# Motherboard.net
KiCad netlist of a schematic drawn in Altium Designer
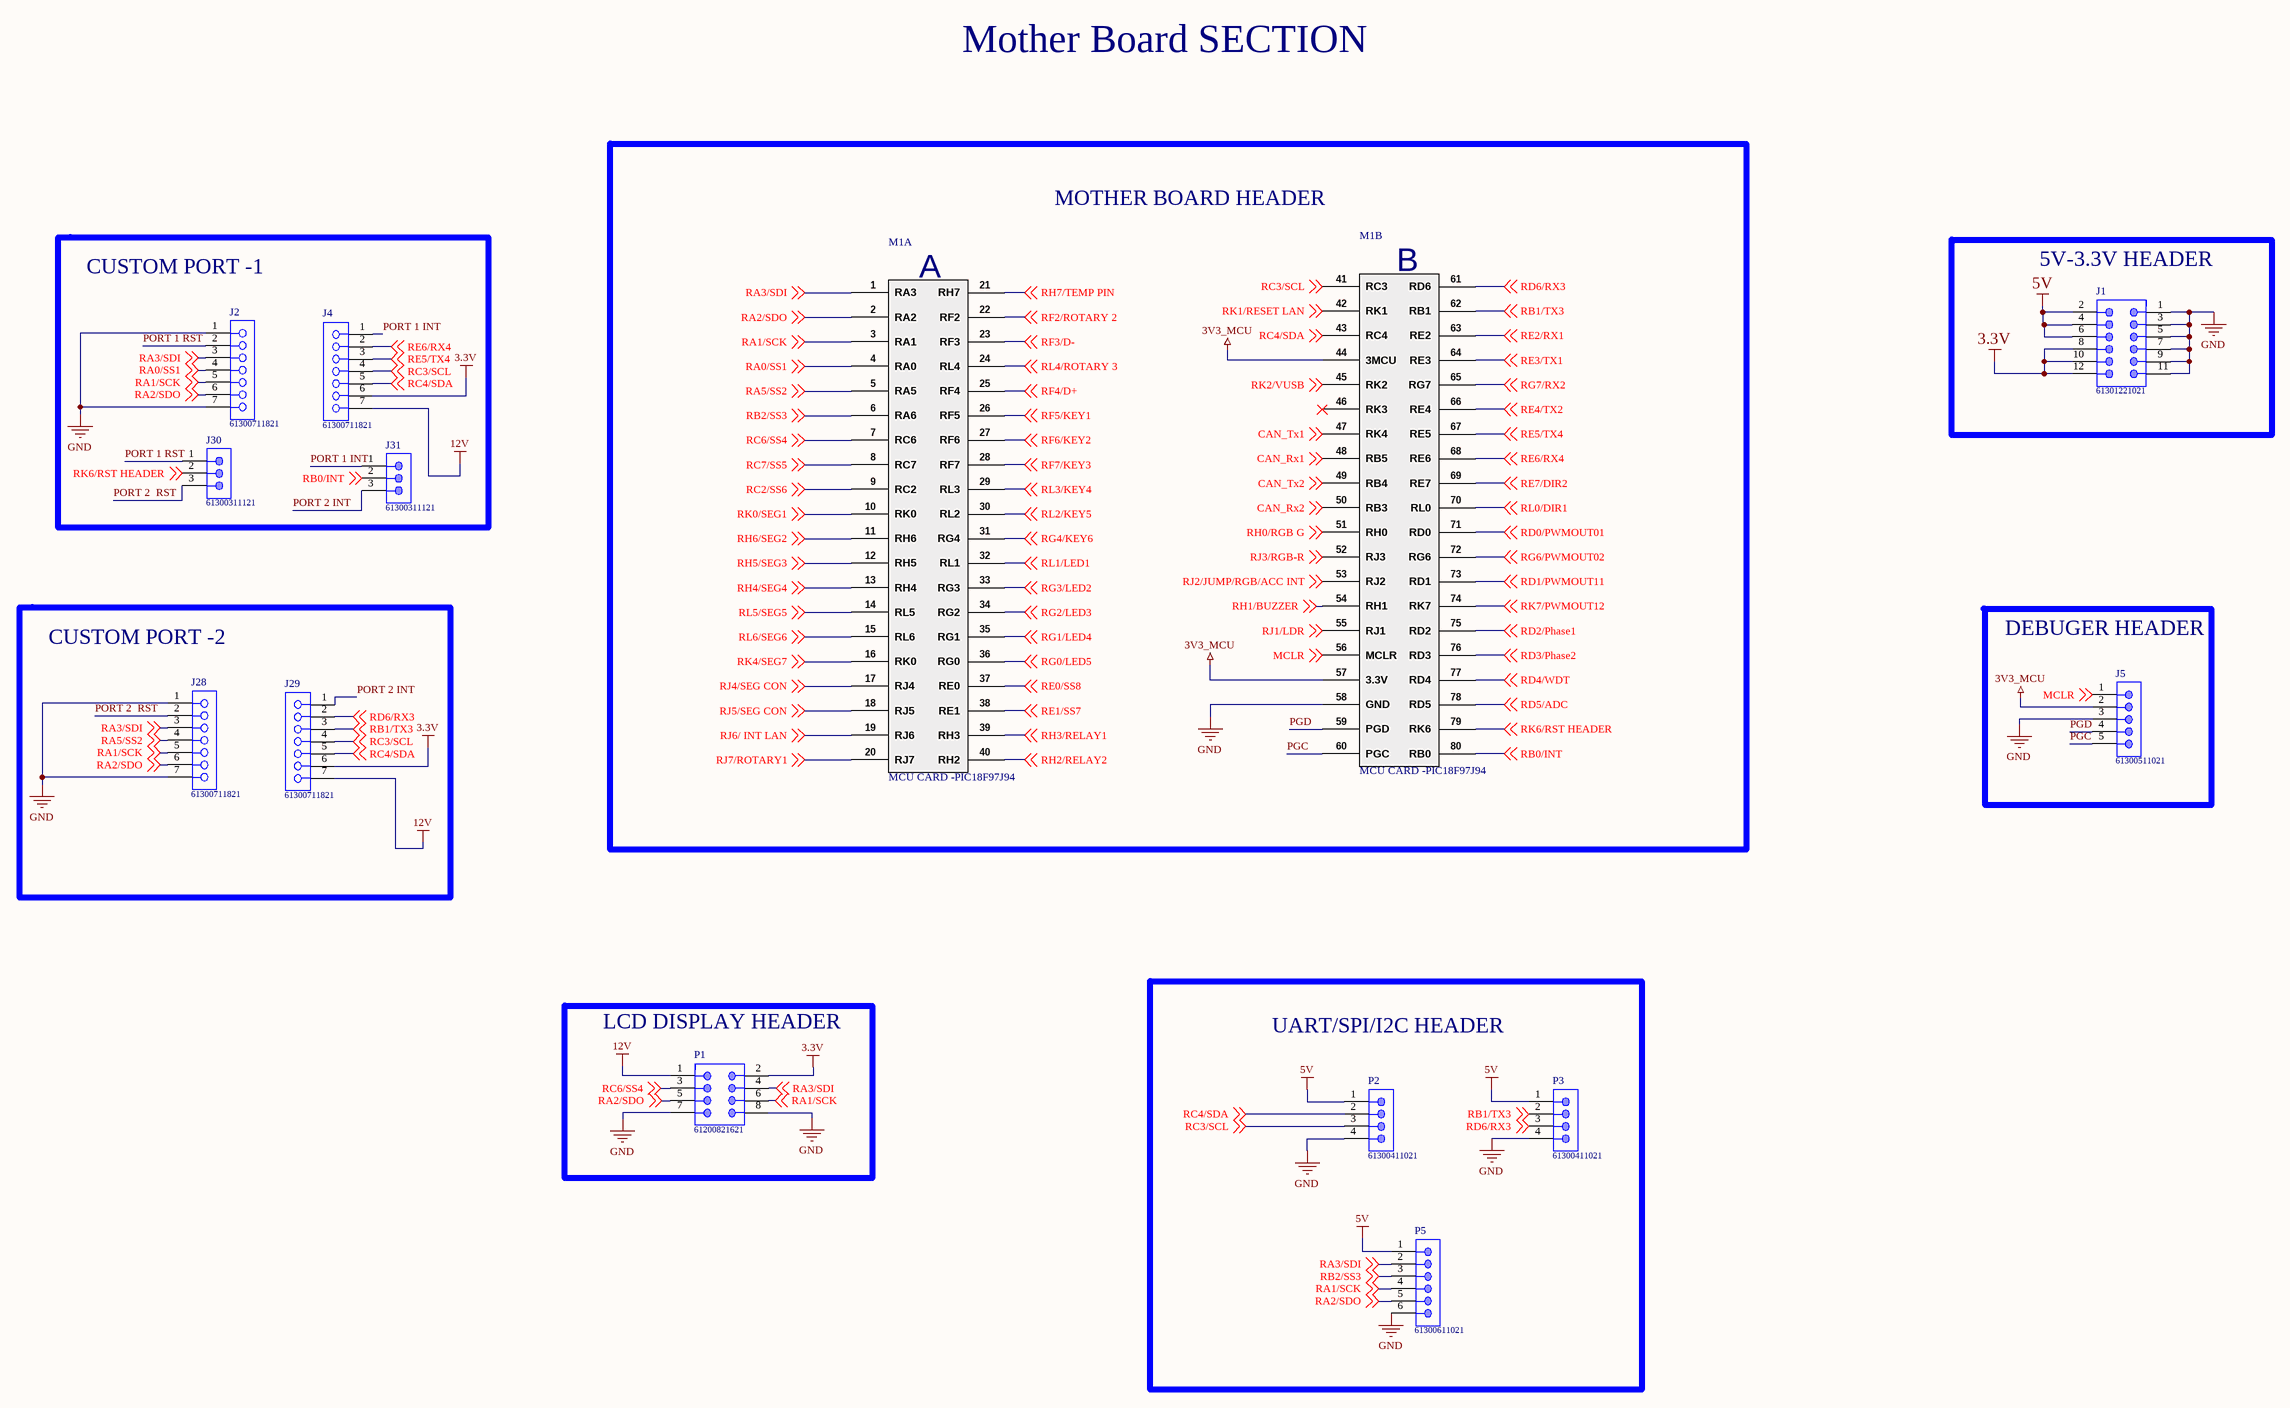
[diagram p0: Motherboard.SchDoc]

(export (version "E")
  (design (tool "Eeschema 10.0.6"))
  (components
    (comp (ref "J1")
      (value "61301221021")
      (footprint "61301221021")
      (description "WR-PHD Pin Header, THT, pitch 2.54mm, Dual Row, Angled, 12pin")
      (fields (field (name "PUBLISHER") "Wurth Elektronik"))
      (libsource (lib "SIL_Connectors WR-PHD_rev19a") (part "61301221021"))
    )
    (comp (ref "J2")
      (value "61300711821")
      (footprint "61300711821")
      (description "WR-PHD Socket Header, THT, pitch 2.54mm, Single Row, Vertical, 7pin")
      (fields (field (name "PUBLISHER") "Wurth Elektronik"))
      (libsource (lib "SIL_Connectors WR-PHD_rev19a") (part "61300711821"))
    )
    (comp (ref "J4")
      (value "61300711821")
      (footprint "61300711821")
      (description "WR-PHD Socket Header, THT, pitch 2.54mm, Single Row, Vertical, 7pin")
      (fields (field (name "PUBLISHER") "Wurth Elektronik"))
      (libsource (lib "SIL_Connectors WR-PHD_rev19a") (part "61300711821"))
    )
    (comp (ref "J5")
      (value "61300511021")
      (footprint "61300511021")
      (description "WR-PHD Pin Header, THT, pitch 2.54mm, Single Row, Angled, 5pin")
      (fields (field (name "PUBLISHER") "Wurth Elektronik"))
      (libsource (lib "SIL_Connectors WR-PHD_rev19a") (part "61300511021"))
    )
    (comp (ref "J28")
      (value "61300711821")
      (footprint "61300711821")
      (description "WR-PHD Socket Header, THT, pitch 2.54mm, Single Row, Vertical, 7pin")
      (fields (field (name "PUBLISHER") "Wurth Elektronik"))
      (libsource (lib "SIL_Connectors WR-PHD_rev19a") (part "61300711821"))
    )
    (comp (ref "J29")
      (value "61300711821")
      (footprint "61300711821")
      (description "WR-PHD Socket Header, THT, pitch 2.54mm, Single Row, Vertical, 7pin")
      (fields (field (name "PUBLISHER") "Wurth Elektronik"))
      (libsource (lib "SIL_Connectors WR-PHD_rev19a") (part "61300711821"))
    )
    (comp (ref "J30")
      (value "61300311121")
      (footprint "61300311121")
      (description "WR-PHD Pin Header, THT, pitch 2.54mm, Single Row, Vertical, 3pin")
      (fields (field (name "PUBLISHER") "Wurth Elektronik"))
      (libsource (lib "SIL_Connectors WR-PHD_rev19a") (part "61300311121"))
    )
    (comp (ref "J31")
      (value "61300311121")
      (footprint "61300311121")
      (description "WR-PHD Pin Header, THT, pitch 2.54mm, Single Row, Vertical, 3pin")
      (fields (field (name "PUBLISHER") "Wurth Elektronik"))
      (libsource (lib "SIL_Connectors WR-PHD_rev19a") (part "61300311121"))
    )
    (comp (ref "M1")
      (value "MCU CARD -PIC18F97J94")
      (footprint "MCU-Card-PIC18f97j94")
      (description "MCU CARD -PIC18F97J94 FOR mother board")
      (libsource (lib "Abhi components") (part "MCU CARD -PIC18F97J94"))
    )
    (comp (ref "P1")
      (value "61200821621")
      (footprint "61200821621")
      (description "Male Box Header WR-BHD, THT, Vertical, pitch 2.54 mm, 8 pins")
      (fields (field (name "PUBLISHER") "Wurth Elektronik"))
      (libsource (lib "FRC Male BOX Header straight") (part "61200821621"))
    )
    (comp (ref "P2")
      (value "61300411021")
      (footprint "61300411021")
      (description "WR-PHD Pin Header, THT, pitch 2.54mm, Single Row, Angled, 4pin")
      (fields (field (name "PUBLISHER") "Wurth Elektronik"))
      (libsource (lib "SIL_Connectors WR-PHD_rev19a") (part "61300411021"))
    )
    (comp (ref "P3")
      (value "61300411021")
      (footprint "61300411021")
      (description "WR-PHD Pin Header, THT, pitch 2.54mm, Single Row, Angled, 4pin")
      (fields (field (name "PUBLISHER") "Wurth Elektronik"))
      (libsource (lib "SIL_Connectors WR-PHD_rev19a") (part "61300411021"))
    )
    (comp (ref "P5")
      (value "61300611021")
      (footprint "61300611021")
      (description "WR-PHD Pin Header, THT, pitch 2.54mm, Single Row, Angled, 6pin")
      (fields (field (name "PUBLISHER") "Wurth Elektronik"))
      (libsource (lib "SIL_Connectors WR-PHD_rev19a") (part "61300611021"))
    )
  )
  (nets
    (net (code "1") (name "/PGC") (class "Default")
      (node (ref "J5") (pin "5") (pinfunction "5_5") (pintype "passive"))
      (node (ref "M1") (pin "60") (pinfunction "PGC_60") (pintype "passive"))
    )
    (net (code "2") (name "/PGD") (class "Default")
      (node (ref "J5") (pin "4") (pinfunction "4_4") (pintype "passive"))
      (node (ref "M1") (pin "59") (pinfunction "PGD_59") (pintype "passive"))
    )
    (net (code "3") (name "/PORT 1 INT") (class "Default")
      (node (ref "J31") (pin "1") (pinfunction "1_1") (pintype "passive"))
      (node (ref "J4") (pin "1") (pinfunction "1_1") (pintype "passive"))
    )
    (net (code "4") (name "/PORT 1 RST") (class "Default")
      (node (ref "J2") (pin "2") (pinfunction "2_2") (pintype "passive"))
      (node (ref "J30") (pin "1") (pinfunction "1_1") (pintype "passive"))
    )
    (net (code "5") (name "/PORT 2  RST") (class "Default")
      (node (ref "J28") (pin "2") (pinfunction "2_2") (pintype "passive"))
      (node (ref "J30") (pin "3") (pinfunction "3_3") (pintype "passive"))
    )
    (net (code "6") (name "/PORT 2 INT") (class "Default")
      (node (ref "J29") (pin "1") (pinfunction "1_1") (pintype "passive"))
      (node (ref "J31") (pin "3") (pinfunction "3_3") (pintype "passive"))
    )
    (net (code "7") (name "3.3V") (class "Default")
      (node (ref "J1") (pin "10") (pinfunction "10_10") (pintype "passive"))
      (node (ref "J1") (pin "12") (pinfunction "12_12") (pintype "passive"))
      (node (ref "J1") (pin "8") (pinfunction "8_8") (pintype "passive"))
      (node (ref "J29") (pin "6") (pinfunction "6_6") (pintype "passive"))
      (node (ref "J4") (pin "6") (pinfunction "6_6") (pintype "passive"))
      (node (ref "P1") (pin "2") (pinfunction "2_2") (pintype "passive"))
    )
    (net (code "8") (name "3V3_MCU") (class "Default")
      (node (ref "J5") (pin "2") (pinfunction "2_2") (pintype "passive"))
      (node (ref "M1") (pin "44") (pinfunction "3MCU_44") (pintype "passive"))
      (node (ref "M1") (pin "57") (pinfunction "3.3V_57") (pintype "passive"))
    )
    (net (code "9") (name "5V") (class "Default")
      (node (ref "J1") (pin "2") (pinfunction "2_2") (pintype "passive"))
      (node (ref "J1") (pin "4") (pinfunction "4_4") (pintype "passive"))
      (node (ref "J1") (pin "6") (pinfunction "6_6") (pintype "passive"))
      (node (ref "P2") (pin "1") (pinfunction "1_1") (pintype "passive"))
      (node (ref "P3") (pin "1") (pinfunction "1_1") (pintype "passive"))
      (node (ref "P5") (pin "1") (pinfunction "1_1") (pintype "passive"))
    )
    (net (code "10") (name "12V") (class "Default")
      (node (ref "J29") (pin "7") (pinfunction "7_7") (pintype "passive"))
      (node (ref "J4") (pin "7") (pinfunction "7_7") (pintype "passive"))
      (node (ref "P1") (pin "1") (pinfunction "1_1") (pintype "passive"))
    )
    (net (code "11") (name "CAN_Rx1") (class "Default")
      (node (ref "M1") (pin "48") (pinfunction "RB5_48") (pintype "passive"))
    )
    (net (code "12") (name "CAN_Rx2") (class "Default")
      (node (ref "M1") (pin "50") (pinfunction "RB3_50") (pintype "passive"))
    )
    (net (code "13") (name "CAN_Tx1") (class "Default")
      (node (ref "M1") (pin "47") (pinfunction "RK4_47") (pintype "passive"))
    )
    (net (code "14") (name "CAN_Tx2") (class "Default")
      (node (ref "M1") (pin "49") (pinfunction "RB4_49") (pintype "passive"))
    )
    (net (code "15") (name "GND") (class "Default")
      (node (ref "J1") (pin "1") (pinfunction "1_1") (pintype "passive"))
      (node (ref "J1") (pin "11") (pinfunction "11_11") (pintype "passive"))
      (node (ref "J1") (pin "3") (pinfunction "3_3") (pintype "passive"))
      (node (ref "J1") (pin "5") (pinfunction "5_5") (pintype "passive"))
      (node (ref "J1") (pin "7") (pinfunction "7_7") (pintype "passive"))
      (node (ref "J1") (pin "9") (pinfunction "9_9") (pintype "passive"))
      (node (ref "J2") (pin "1") (pinfunction "1_1") (pintype "passive"))
      (node (ref "J2") (pin "7") (pinfunction "7_7") (pintype "passive"))
      (node (ref "J28") (pin "1") (pinfunction "1_1") (pintype "passive"))
      (node (ref "J28") (pin "7") (pinfunction "7_7") (pintype "passive"))
      (node (ref "J5") (pin "3") (pinfunction "3_3") (pintype "passive"))
      (node (ref "M1") (pin "58") (pinfunction "GND_58") (pintype "passive"))
      (node (ref "P1") (pin "7") (pinfunction "7_7") (pintype "passive"))
      (node (ref "P1") (pin "8") (pinfunction "8_8") (pintype "passive"))
      (node (ref "P2") (pin "4") (pinfunction "4_4") (pintype "passive"))
      (node (ref "P3") (pin "4") (pinfunction "4_4") (pintype "passive"))
      (node (ref "P5") (pin "6") (pinfunction "6_6") (pintype "passive"))
    )
    (net (code "16") (name "MCLR") (class "Default")
      (node (ref "J5") (pin "1") (pinfunction "1_1") (pintype "passive"))
      (node (ref "M1") (pin "56") (pinfunction "MCLR_56") (pintype "passive"))
    )
    (net (code "17") (name "RA0{slash}SS1") (class "Default")
      (node (ref "J2") (pin "4") (pinfunction "4_4") (pintype "passive"))
      (node (ref "M1") (pin "4") (pinfunction "RA0_4") (pintype "passive"))
    )
    (net (code "18") (name "RA1{slash}SCK") (class "Default")
      (node (ref "J2") (pin "5") (pinfunction "5_5") (pintype "passive"))
      (node (ref "J28") (pin "5") (pinfunction "5_5") (pintype "passive"))
      (node (ref "M1") (pin "3") (pinfunction "RA1_3") (pintype "passive"))
      (node (ref "P1") (pin "6") (pinfunction "6_6") (pintype "passive"))
      (node (ref "P5") (pin "4") (pinfunction "4_4") (pintype "passive"))
    )
    (net (code "19") (name "RA2{slash}SDO") (class "Default")
      (node (ref "J2") (pin "6") (pinfunction "6_6") (pintype "passive"))
      (node (ref "J28") (pin "6") (pinfunction "6_6") (pintype "passive"))
      (node (ref "M1") (pin "2") (pinfunction "RA2_2") (pintype "passive"))
      (node (ref "P1") (pin "5") (pinfunction "5_5") (pintype "passive"))
      (node (ref "P5") (pin "5") (pinfunction "5_5") (pintype "passive"))
    )
    (net (code "20") (name "RA3{slash}SDI") (class "Default")
      (node (ref "J2") (pin "3") (pinfunction "3_3") (pintype "passive"))
      (node (ref "J28") (pin "3") (pinfunction "3_3") (pintype "passive"))
      (node (ref "M1") (pin "1") (pinfunction "RA3_1") (pintype "passive"))
      (node (ref "P1") (pin "4") (pinfunction "4_4") (pintype "passive"))
      (node (ref "P5") (pin "2") (pinfunction "2_2") (pintype "passive"))
    )
    (net (code "21") (name "RA5{slash}SS2") (class "Default")
      (node (ref "J28") (pin "4") (pinfunction "4_4") (pintype "passive"))
      (node (ref "M1") (pin "5") (pinfunction "RA5_5") (pintype "passive"))
    )
    (net (code "22") (name "RB0{slash}INT") (class "Default")
      (node (ref "J31") (pin "2") (pinfunction "2_2") (pintype "passive"))
      (node (ref "M1") (pin "80") (pinfunction "RB0_80") (pintype "passive"))
    )
    (net (code "23") (name "RB1{slash}TX3") (class "Default")
      (node (ref "J29") (pin "3") (pinfunction "3_3") (pintype "passive"))
      (node (ref "M1") (pin "62") (pinfunction "RB1_62") (pintype "passive"))
      (node (ref "P3") (pin "2") (pinfunction "2_2") (pintype "passive"))
    )
    (net (code "24") (name "RB2{slash}SS3") (class "Default")
      (node (ref "M1") (pin "6") (pinfunction "RA6_6") (pintype "passive"))
      (node (ref "P5") (pin "3") (pinfunction "3_3") (pintype "passive"))
    )
    (net (code "25") (name "RC2{slash}SS6") (class "Default")
      (node (ref "M1") (pin "9") (pinfunction "RC2_9") (pintype "passive"))
    )
    (net (code "26") (name "RC3{slash}SCL") (class "Default")
      (node (ref "J29") (pin "4") (pinfunction "4_4") (pintype "passive"))
      (node (ref "J4") (pin "4") (pinfunction "4_4") (pintype "passive"))
      (node (ref "M1") (pin "41") (pinfunction "RC3_41") (pintype "passive"))
      (node (ref "P2") (pin "3") (pinfunction "3_3") (pintype "passive"))
    )
    (net (code "27") (name "RC4{slash}SDA") (class "Default")
      (node (ref "J29") (pin "5") (pinfunction "5_5") (pintype "passive"))
      (node (ref "J4") (pin "5") (pinfunction "5_5") (pintype "passive"))
      (node (ref "M1") (pin "43") (pinfunction "RC4_43") (pintype "passive"))
      (node (ref "P2") (pin "2") (pinfunction "2_2") (pintype "passive"))
    )
    (net (code "28") (name "RC6{slash}SS4") (class "Default")
      (node (ref "M1") (pin "7") (pinfunction "RC6_7") (pintype "passive"))
      (node (ref "P1") (pin "3") (pinfunction "3_3") (pintype "passive"))
    )
    (net (code "29") (name "RC7{slash}SS5") (class "Default")
      (node (ref "M1") (pin "8") (pinfunction "RC7_8") (pintype "passive"))
    )
    (net (code "30") (name "RD0{slash}PWMOUT01") (class "Default")
      (node (ref "M1") (pin "71") (pinfunction "RD0_71") (pintype "passive"))
    )
    (net (code "31") (name "RD1{slash}PWMOUT11") (class "Default")
      (node (ref "M1") (pin "73") (pinfunction "RD1_73") (pintype "passive"))
    )
    (net (code "32") (name "RD2{slash}Phase1") (class "Default")
      (node (ref "M1") (pin "75") (pinfunction "RD2_75") (pintype "passive"))
    )
    (net (code "33") (name "RD3{slash}Phase2") (class "Default")
      (node (ref "M1") (pin "76") (pinfunction "RD3_76") (pintype "passive"))
    )
    (net (code "34") (name "RD4{slash}WDT") (class "Default")
      (node (ref "M1") (pin "77") (pinfunction "RD4_77") (pintype "passive"))
    )
    (net (code "35") (name "RD5{slash}ADC") (class "Default")
      (node (ref "M1") (pin "78") (pinfunction "RD5_78") (pintype "passive"))
    )
    (net (code "36") (name "RD6{slash}RX3") (class "Default")
      (node (ref "J29") (pin "2") (pinfunction "2_2") (pintype "passive"))
      (node (ref "M1") (pin "61") (pinfunction "RD6_61") (pintype "passive"))
      (node (ref "P3") (pin "3") (pinfunction "3_3") (pintype "passive"))
    )
    (net (code "37") (name "RE0{slash}SS8") (class "Default")
      (node (ref "M1") (pin "37") (pinfunction "RE0_37") (pintype "passive"))
    )
    (net (code "38") (name "RE1{slash}SS7") (class "Default")
      (node (ref "M1") (pin "38") (pinfunction "RE1_38") (pintype "passive"))
    )
    (net (code "39") (name "RE2{slash}RX1") (class "Default")
      (node (ref "M1") (pin "63") (pinfunction "RE2_63") (pintype "passive"))
    )
    (net (code "40") (name "RE3{slash}TX1") (class "Default")
      (node (ref "M1") (pin "64") (pinfunction "RE3_64") (pintype "passive"))
    )
    (net (code "41") (name "RE4{slash}TX2") (class "Default")
      (node (ref "M1") (pin "66") (pinfunction "RE4_66") (pintype "passive"))
    )
    (net (code "42") (name "RE5{slash}TX4") (class "Default")
      (node (ref "J4") (pin "3") (pinfunction "3_3") (pintype "passive"))
      (node (ref "M1") (pin "67") (pinfunction "RE5_67") (pintype "passive"))
    )
    (net (code "43") (name "RE6{slash}RX4") (class "Default")
      (node (ref "J4") (pin "2") (pinfunction "2_2") (pintype "passive"))
      (node (ref "M1") (pin "68") (pinfunction "RE6_68") (pintype "passive"))
    )
    (net (code "44") (name "RE7{slash}DIR2") (class "Default")
      (node (ref "M1") (pin "69") (pinfunction "RE7_69") (pintype "passive"))
    )
    (net (code "45") (name "RF2{slash}ROTARY 2") (class "Default")
      (node (ref "M1") (pin "22") (pinfunction "RF2_22") (pintype "passive"))
    )
    (net (code "46") (name "RF3{slash}D-") (class "Default")
      (node (ref "M1") (pin "23") (pinfunction "RF3_23") (pintype "passive"))
    )
    (net (code "47") (name "RF4{slash}D+") (class "Default")
      (node (ref "M1") (pin "25") (pinfunction "RF4_25") (pintype "passive"))
    )
    (net (code "48") (name "RF5{slash}KEY1") (class "Default")
      (node (ref "M1") (pin "26") (pinfunction "RF5_26") (pintype "passive"))
    )
    (net (code "49") (name "RF6{slash}KEY2") (class "Default")
      (node (ref "M1") (pin "27") (pinfunction "RF6_27") (pintype "passive"))
    )
    (net (code "50") (name "RF7{slash}KEY3") (class "Default")
      (node (ref "M1") (pin "28") (pinfunction "RF7_28") (pintype "passive"))
    )
    (net (code "51") (name "RG0{slash}LED5") (class "Default")
      (node (ref "M1") (pin "36") (pinfunction "RG0_36") (pintype "passive"))
    )
    (net (code "52") (name "RG1{slash}LED4") (class "Default")
      (node (ref "M1") (pin "35") (pinfunction "RG1_35") (pintype "passive"))
    )
    (net (code "53") (name "RG2{slash}LED3") (class "Default")
      (node (ref "M1") (pin "34") (pinfunction "RG2_34") (pintype "passive"))
    )
    (net (code "54") (name "RG3{slash}LED2") (class "Default")
      (node (ref "M1") (pin "33") (pinfunction "RG3_33") (pintype "passive"))
    )
    (net (code "55") (name "RG4{slash}KEY6") (class "Default")
      (node (ref "M1") (pin "31") (pinfunction "RG4_31") (pintype "passive"))
    )
    (net (code "56") (name "RG6{slash}PWMOUT02") (class "Default")
      (node (ref "M1") (pin "72") (pinfunction "RG6_72") (pintype "passive"))
    )
    (net (code "57") (name "RG7{slash}RX2") (class "Default")
      (node (ref "M1") (pin "65") (pinfunction "RG7_65") (pintype "passive"))
    )
    (net (code "58") (name "RH0{slash}RGB G") (class "Default")
      (node (ref "M1") (pin "51") (pinfunction "RH0_51") (pintype "passive"))
    )
    (net (code "59") (name "RH1{slash}BUZZER") (class "Default")
      (node (ref "M1") (pin "54") (pinfunction "RH1_54") (pintype "passive"))
    )
    (net (code "60") (name "RH2{slash}RELAY2") (class "Default")
      (node (ref "M1") (pin "40") (pinfunction "RH2_40") (pintype "passive"))
    )
    (net (code "61") (name "RH3{slash}RELAY1") (class "Default")
      (node (ref "M1") (pin "39") (pinfunction "RH3_39") (pintype "passive"))
    )
    (net (code "62") (name "RH4{slash}SEG4") (class "Default")
      (node (ref "M1") (pin "13") (pinfunction "RH4_13") (pintype "passive"))
    )
    (net (code "63") (name "RH5{slash}SEG3") (class "Default")
      (node (ref "M1") (pin "12") (pinfunction "RH5_12") (pintype "passive"))
    )
    (net (code "64") (name "RH6{slash}SEG2") (class "Default")
      (node (ref "M1") (pin "11") (pinfunction "RH6_11") (pintype "passive"))
    )
    (net (code "65") (name "RH7{slash}TEMP PIN") (class "Default")
      (node (ref "M1") (pin "21") (pinfunction "RH7_21") (pintype "passive"))
    )
    (net (code "66") (name "RJ1{slash}LDR") (class "Default")
      (node (ref "M1") (pin "55") (pinfunction "RJ1_55") (pintype "passive"))
    )
    (net (code "67") (name "RJ2{slash}JUMP{slash}RGB{slash}ACC INT") (class "Default")
      (node (ref "M1") (pin "53") (pinfunction "RJ2_53") (pintype "passive"))
    )
    (net (code "68") (name "RJ3{slash}RGB-R") (class "Default")
      (node (ref "M1") (pin "52") (pinfunction "RJ3_52") (pintype "passive"))
    )
    (net (code "69") (name "RJ4{slash}SEG CON") (class "Default")
      (node (ref "M1") (pin "17") (pinfunction "RJ4_17") (pintype "passive"))
    )
    (net (code "70") (name "RJ5{slash}SEG CON") (class "Default")
      (node (ref "M1") (pin "18") (pinfunction "RJ5_18") (pintype "passive"))
    )
    (net (code "71") (name "RJ6{slash} INT LAN") (class "Default")
      (node (ref "M1") (pin "19") (pinfunction "RJ6_19") (pintype "passive"))
    )
    (net (code "72") (name "RJ7{slash}ROTARY1") (class "Default")
      (node (ref "M1") (pin "20") (pinfunction "RJ7_20") (pintype "passive"))
    )
    (net (code "73") (name "RK0{slash}SEG1") (class "Default")
      (node (ref "M1") (pin "10") (pinfunction "RK0_10") (pintype "passive"))
    )
    (net (code "74") (name "RK1{slash}RESET LAN") (class "Default")
      (node (ref "M1") (pin "42") (pinfunction "RK1_42") (pintype "passive"))
    )
    (net (code "75") (name "RK2{slash}VUSB") (class "Default")
      (node (ref "M1") (pin "45") (pinfunction "RK2_45") (pintype "passive"))
    )
    (net (code "76") (name "RK4{slash}SEG7") (class "Default")
      (node (ref "M1") (pin "16") (pinfunction "RK0_16") (pintype "passive"))
    )
    (net (code "77") (name "RK6{slash}RST HEADER") (class "Default")
      (node (ref "J30") (pin "2") (pinfunction "2_2") (pintype "passive"))
      (node (ref "M1") (pin "79") (pinfunction "RK6_79") (pintype "passive"))
    )
    (net (code "78") (name "RK7{slash}PWMOUT12") (class "Default")
      (node (ref "M1") (pin "74") (pinfunction "RK7_74") (pintype "passive"))
    )
    (net (code "79") (name "RL0{slash}DIR1") (class "Default")
      (node (ref "M1") (pin "70") (pinfunction "RL0_70") (pintype "passive"))
    )
    (net (code "80") (name "RL1{slash}LED1") (class "Default")
      (node (ref "M1") (pin "32") (pinfunction "RL1_32") (pintype "passive"))
    )
    (net (code "81") (name "RL2{slash}KEY5") (class "Default")
      (node (ref "M1") (pin "30") (pinfunction "RL2_30") (pintype "passive"))
    )
    (net (code "82") (name "RL3{slash}KEY4") (class "Default")
      (node (ref "M1") (pin "29") (pinfunction "RL3_29") (pintype "passive"))
    )
    (net (code "83") (name "RL4{slash}ROTARY 3") (class "Default")
      (node (ref "M1") (pin "24") (pinfunction "RL4_24") (pintype "passive"))
    )
    (net (code "84") (name "RL5{slash}SEG5") (class "Default")
      (node (ref "M1") (pin "14") (pinfunction "RL5_14") (pintype "passive"))
    )
    (net (code "85") (name "RL6{slash}SEG6") (class "Default")
      (node (ref "M1") (pin "15") (pinfunction "RL6_15") (pintype "passive"))
    )
    (net (code "86") (name "unconnected-(M1B-RK3-Pad46)") (class "Default")
      (node (ref "M1") (pin "46") (pinfunction "RK3_46") (pintype "passive+no_connect"))
    )
  )
)
